# rf24_shield.net
KiCad netlist of a schematic drawn in EAGLE
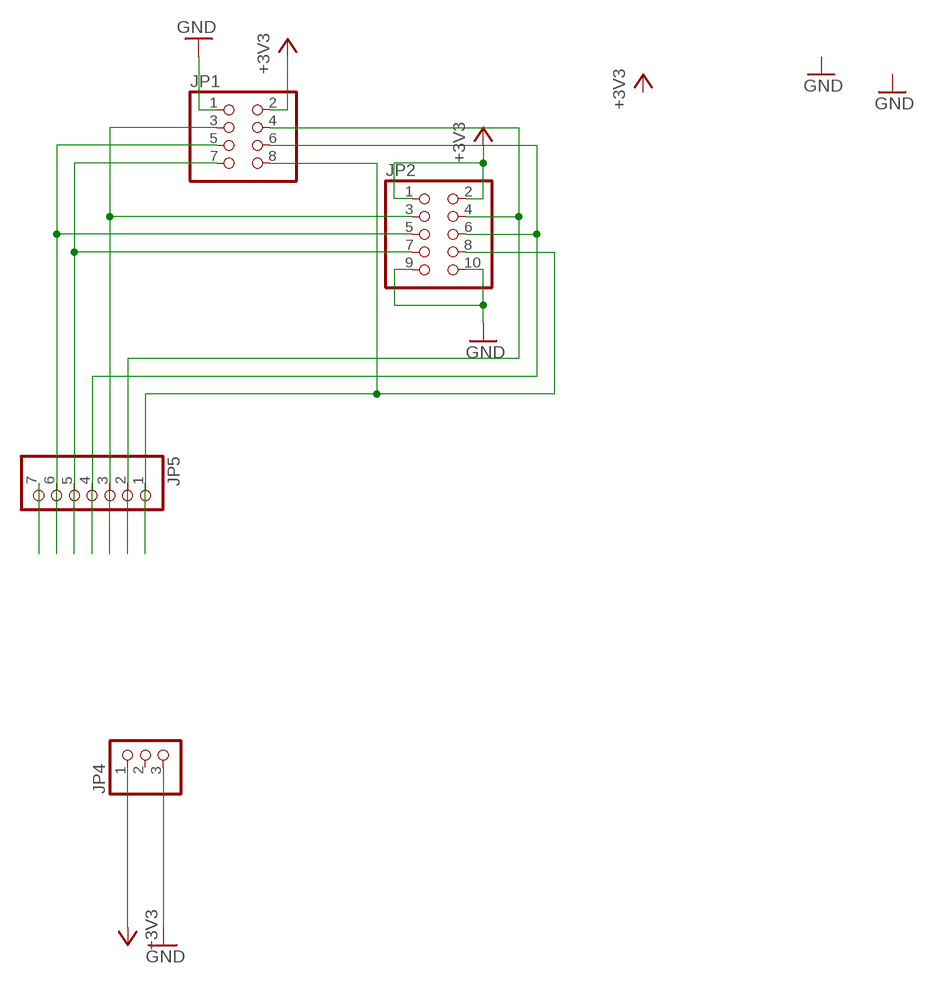
[diagram p0: schematic, sheet 1]

(export (version "E")
  (design (tool "Eeschema 10.0.6"))
  (components
    (comp (ref "JP1")
      (value "PINHD-2X4")
      (footprint "eagle-import:2X04")
      (libsource (lib "eagle-import") (part "PINHD-2X4"))
    )
    (comp (ref "JP2")
      (value "PINHD-2X5")
      (footprint "eagle-import:2X05")
      (libsource (lib "eagle-import") (part "PINHD-2X5"))
    )
    (comp (ref "JP4")
      (value "PINHD-1X3")
      (footprint "eagle-import:1X03")
      (libsource (lib "eagle-import") (part "PINHD-1X3"))
    )
    (comp (ref "JP5")
      (value "PINHD-1X7")
      (footprint "eagle-import:1X07")
      (libsource (lib "eagle-import") (part "PINHD-1X7"))
    )
  )
  (nets
    (net (code "1") (name "+3V3") (class "Default")
      (node (ref "JP1") (pin "2") (pinfunction "2_2") (pintype "passive"))
      (node (ref "JP2") (pin "1") (pinfunction "1_1") (pintype "passive"))
      (node (ref "JP2") (pin "2") (pinfunction "2_2") (pintype "passive"))
      (node (ref "JP4") (pin "1") (pinfunction "1_1") (pintype "passive"))
    )
    (net (code "2") (name "GND") (class "Default")
      (node (ref "JP1") (pin "1") (pinfunction "1_1") (pintype "passive"))
      (node (ref "JP2") (pin "10") (pinfunction "10_10") (pintype "passive"))
      (node (ref "JP2") (pin "9") (pinfunction "9_9") (pintype "passive"))
      (node (ref "JP4") (pin "3") (pinfunction "3_3") (pintype "passive"))
    )
    (net (code "3") (name "Net-(JP1-Pad3)") (class "Default")
      (node (ref "JP1") (pin "3") (pinfunction "3_3") (pintype "passive"))
      (node (ref "JP2") (pin "3") (pinfunction "3_3") (pintype "passive"))
      (node (ref "JP5") (pin "3") (pinfunction "3_3") (pintype "passive"))
    )
    (net (code "4") (name "Net-(JP1-Pad4)") (class "Default")
      (node (ref "JP1") (pin "4") (pinfunction "4_4") (pintype "passive"))
      (node (ref "JP2") (pin "4") (pinfunction "4_4") (pintype "passive"))
      (node (ref "JP5") (pin "2") (pinfunction "2_2") (pintype "passive"))
    )
    (net (code "5") (name "Net-(JP1-Pad5)") (class "Default")
      (node (ref "JP1") (pin "5") (pinfunction "5_5") (pintype "passive"))
      (node (ref "JP2") (pin "5") (pinfunction "5_5") (pintype "passive"))
      (node (ref "JP5") (pin "6") (pinfunction "6_6") (pintype "passive"))
    )
    (net (code "6") (name "Net-(JP1-Pad6)") (class "Default")
      (node (ref "JP1") (pin "6") (pinfunction "6_6") (pintype "passive"))
      (node (ref "JP2") (pin "6") (pinfunction "6_6") (pintype "passive"))
      (node (ref "JP5") (pin "4") (pinfunction "4_4") (pintype "passive"))
    )
    (net (code "7") (name "Net-(JP1-Pad7)") (class "Default")
      (node (ref "JP1") (pin "7") (pinfunction "7_7") (pintype "passive"))
      (node (ref "JP2") (pin "7") (pinfunction "7_7") (pintype "passive"))
      (node (ref "JP5") (pin "5") (pinfunction "5_5") (pintype "passive"))
    )
    (net (code "8") (name "Net-(JP1-Pad8)") (class "Default")
      (node (ref "JP1") (pin "8") (pinfunction "8_8") (pintype "passive"))
      (node (ref "JP2") (pin "8") (pinfunction "8_8") (pintype "passive"))
      (node (ref "JP5") (pin "1") (pinfunction "1_1") (pintype "passive"))
    )
    (net (code "9") (name "unconnected-(JP4-Pad2)") (class "Default")
      (node (ref "JP4") (pin "2") (pinfunction "2_2") (pintype "passive"))
    )
    (net (code "10") (name "unconnected-(JP5-Pad7)") (class "Default")
      (node (ref "JP5") (pin "7") (pinfunction "7_7") (pintype "passive"))
    )
  )
)
